# Power_Supply.net
KiCad netlist of a schematic drawn in Altium Designer
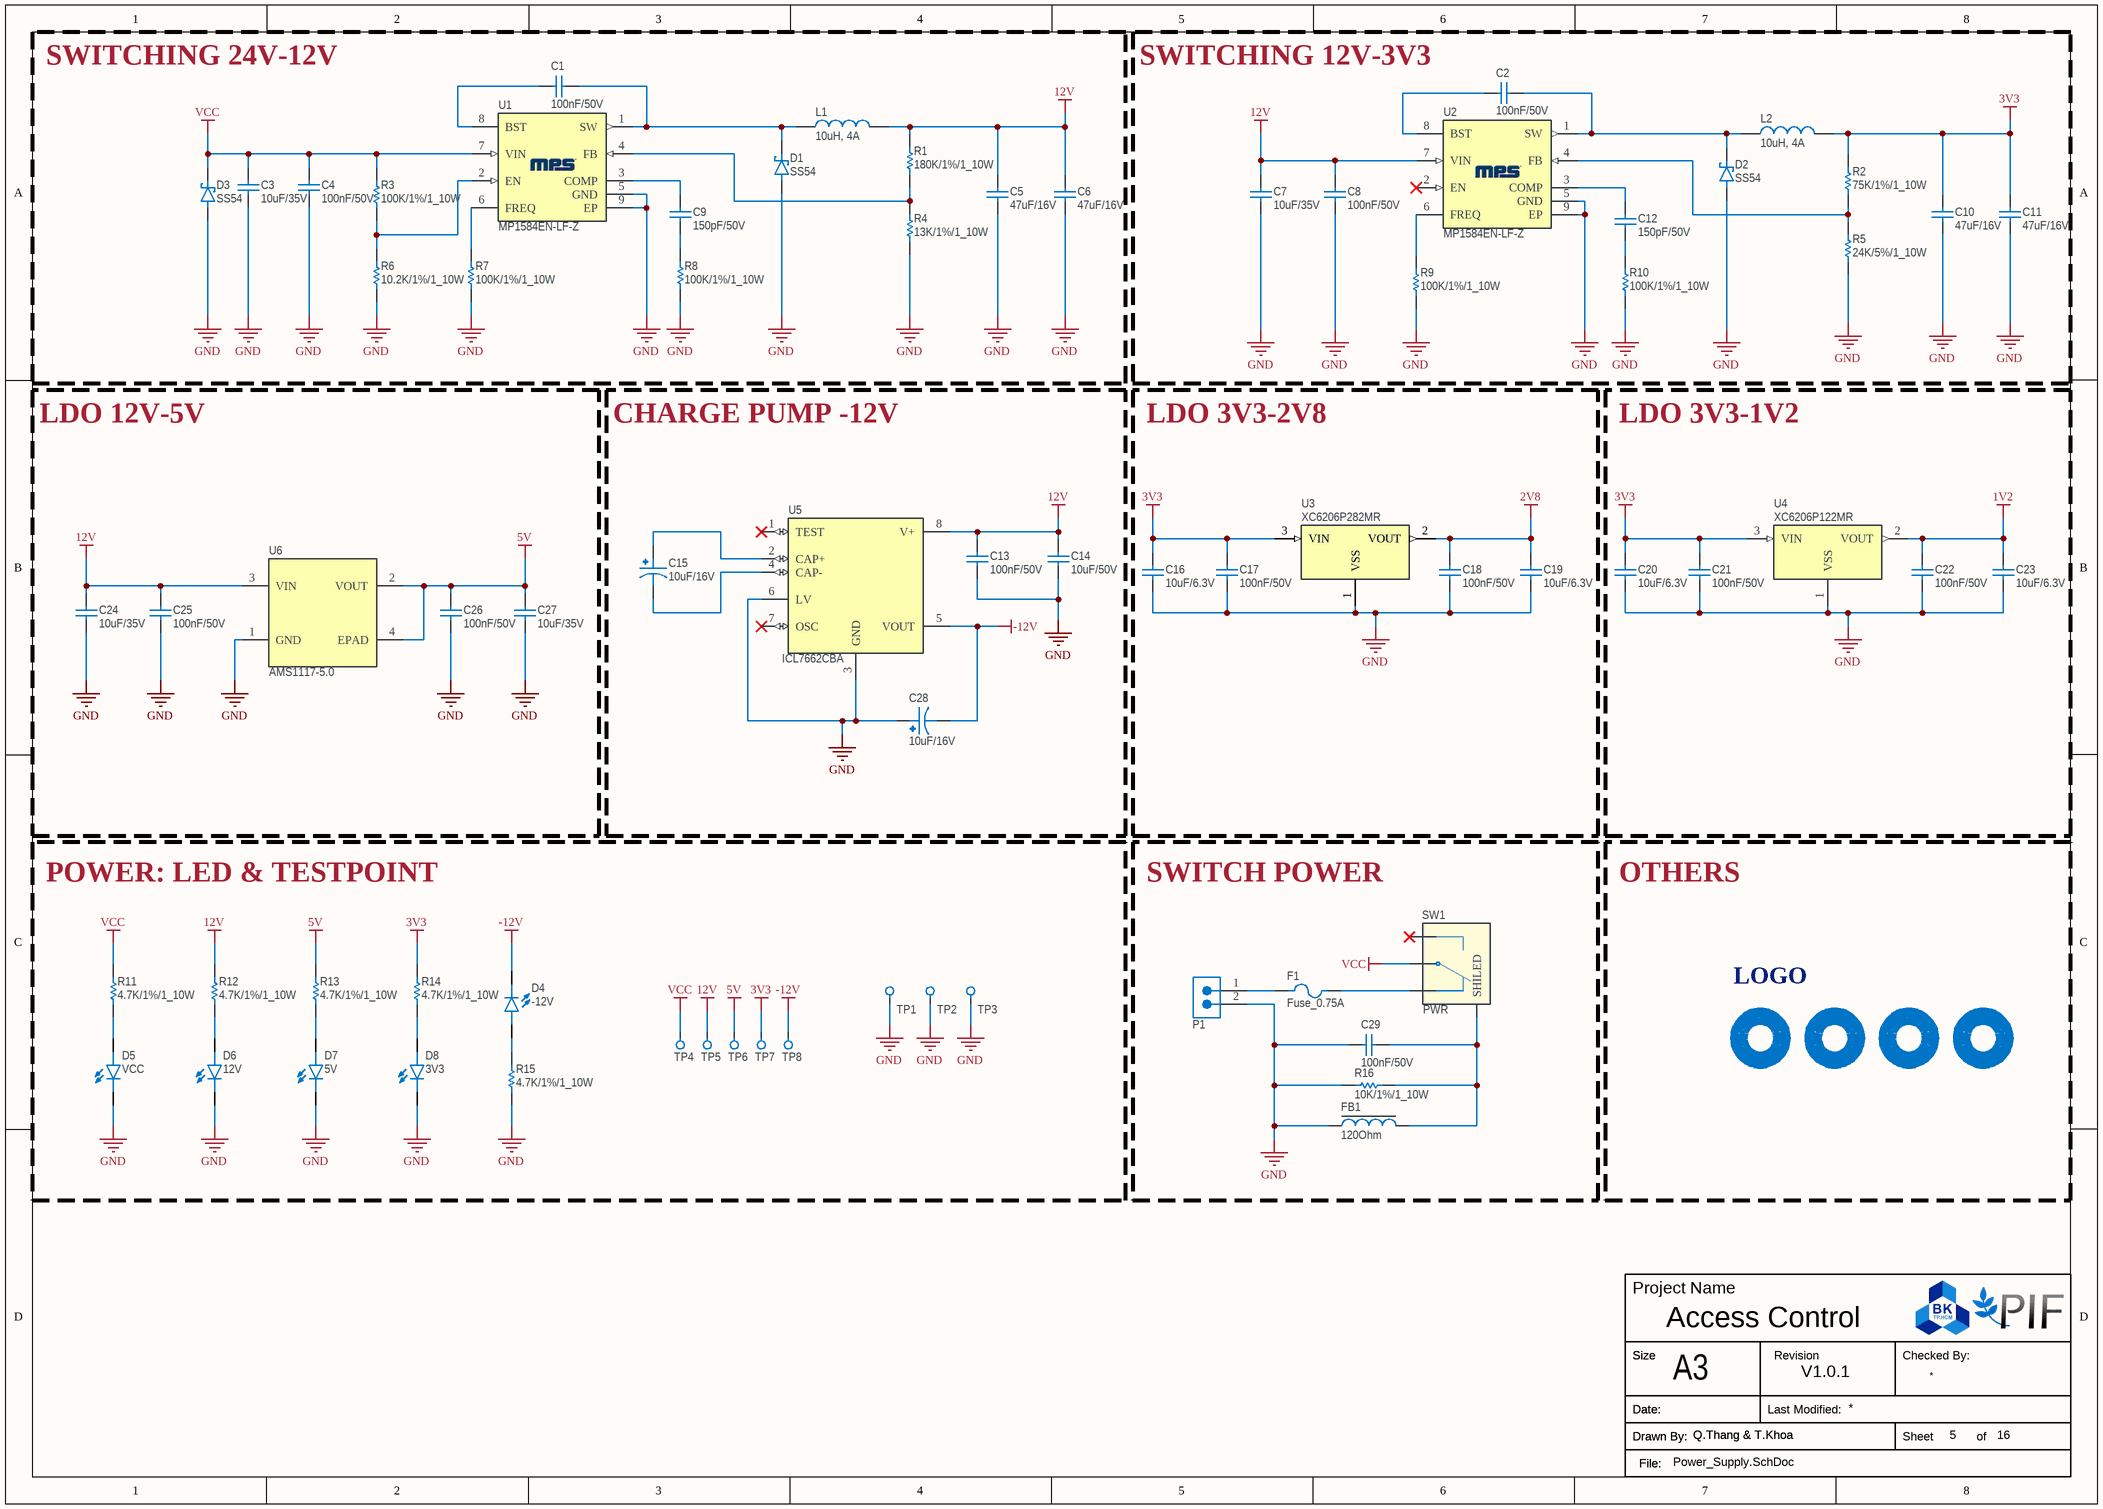
[diagram p0: Power_Supply.SchDoc]

(export (version "E")
  (design (tool "Eeschema 10.0.6"))
  (components
    (comp (ref "*1") (value "LOGO") (footprint "BK_LOGO") (libsource (lib "BluetoothTracking") (part "LOGO")))
    (comp (ref "C1")
      (value "100nF/50V")
      (footprint "CAP_0603")
      (description "CAP, size 0603, 100nF, 50V")
      (fields (field (name "SUPPLY PART NUMBER") "Tụ Gốm 0603 100nF (0.1uF) 50V"))
      (libsource (lib "BluetoothTracking") (part "Ceramic_Cap_100nF_50V_0603"))
    )
    (comp (ref "C2")
      (value "100nF/50V")
      (footprint "CAP_0603")
      (description "CAP, size 0603, 100nF, 50V")
      (fields (field (name "SUPPLY PART NUMBER") "Tụ Gốm 0603 100nF (0.1uF) 50V"))
      (libsource (lib "BluetoothTracking") (part "Ceramic_Cap_100nF_50V_0603"))
    )
    (comp (ref "C3")
      (value "10uF/35V")
      (footprint "CAP_1206")
      (description "CAP, size 1206, 10uF, 35V")
      (fields (field (name "SUPPLY PART NUMBER") "Tụ Gốm 1206 10uF 35V"))
      (libsource (lib "BluetoothTracking") (part "Ceramic_Cap_10uF_35V_1206"))
    )
    (comp (ref "C4")
      (value "100nF/50V")
      (footprint "CAP_1206")
      (description "CAP, size 1206, 100nF, 50V")
      (fields (field (name "SUPPLY PART NUMBER") "Tụ Gốm 1206 100nF (0.1uF) 50V"))
      (libsource (lib "BluetoothTracking") (part "Ceramic_Cap_100nF_50V_1206"))
    )
    (comp (ref "C5")
      (value "47uF/16V")
      (footprint "CAP_1206")
      (description "CAP, size 1206, 47uF, 16V")
      (fields (field (name "SUPPLY PART NUMBER") "Tụ Gốm 1206 47uF 16V"))
      (libsource (lib "BluetoothTracking") (part "Ceramic_Cap_47uF_16V_1206"))
    )
    (comp (ref "C6")
      (value "47uF/16V")
      (footprint "CAP_1206")
      (description "CAP, size 1206, 47uF, 16V")
      (fields (field (name "SUPPLY PART NUMBER") "Tụ Gốm 1206 47uF 16V"))
      (libsource (lib "BluetoothTracking") (part "Ceramic_Cap_47uF_16V_1206"))
    )
    (comp (ref "C7")
      (value "10uF/35V")
      (footprint "CAP_1206")
      (description "CAP, size 1206, 10uF, 35V")
      (fields (field (name "SUPPLY PART NUMBER") "Tụ Gốm 1206 10uF 35V"))
      (libsource (lib "BluetoothTracking") (part "Ceramic_Cap_10uF_35V_1206"))
    )
    (comp (ref "C8")
      (value "100nF/50V")
      (footprint "CAP_1206")
      (description "CAP, size 1206, 100nF, 50V")
      (fields (field (name "SUPPLY PART NUMBER") "Tụ Gốm 1206 100nF (0.1uF) 50V"))
      (libsource (lib "BluetoothTracking") (part "Ceramic_Cap_100nF_50V_1206"))
    )
    (comp (ref "C9")
      (value "150pF/50V")
      (footprint "CAP_0603")
      (description "CAP, size 0603, 150pF, 50V")
      (fields (field (name "SUPPLY PART NUMBER") "Tụ Gốm 0603 150pF 50V"))
      (libsource (lib "BluetoothTracking") (part "Ceramic_Cap_150pF_50V_0603"))
    )
    (comp (ref "C10")
      (value "47uF/16V")
      (footprint "CAP_1206")
      (description "CAP, size 1206, 47uF, 16V")
      (fields (field (name "SUPPLY PART NUMBER") "Tụ Gốm 1206 47uF 16V"))
      (libsource (lib "BluetoothTracking") (part "Ceramic_Cap_47uF_16V_1206"))
    )
    (comp (ref "C11")
      (value "47uF/16V")
      (footprint "CAP_1206")
      (description "CAP, size 1206, 47uF, 16V")
      (fields (field (name "SUPPLY PART NUMBER") "Tụ Gốm 1206 47uF 16V"))
      (libsource (lib "BluetoothTracking") (part "Ceramic_Cap_47uF_16V_1206"))
    )
    (comp (ref "C12")
      (value "150pF/50V")
      (footprint "CAP_0603")
      (description "CAP, size 0603, 150pF, 50V")
      (fields (field (name "SUPPLY PART NUMBER") "Tụ Gốm 0603 150pF 50V"))
      (libsource (lib "BluetoothTracking") (part "Ceramic_Cap_150pF_50V_0603"))
    )
    (comp (ref "C13")
      (value "100nF/50V")
      (footprint "CAP_0805")
      (description "CAP, size 0805, 100nF, 50V")
      (fields (field (name "SUPPLY PART NUMBER") "Tụ Gốm 0805 100nF (0.1uF) 50V"))
      (libsource (lib "BluetoothTracking") (part "Ceramic_Cap_100nF_50V_0805"))
    )
    (comp (ref "C14")
      (value "10uF/50V")
      (footprint "CAP_0805")
      (description "CAP, size 0805, 10uF, 50V")
      (fields (field (name "SUPPLY PART NUMBER") "Tụ Gốm 0805 10uF 50V"))
      (libsource (lib "BluetoothTracking") (part "Ceramic_Cap_10uF_50V_0805"))
    )
    (comp (ref "C15")
      (value "10uF/16V")
      (footprint "TanTa_Cap_A")
      (description "Tantalum Capacitors 10uF 16V 1206")
      (fields (field (name "SUPPLY PART NUMBER") "AVX"))
      (libsource (lib "") (part "Tanta_Cap_10uF_16V_1206_1"))
    )
    (comp (ref "C16")
      (value "10uF/6.3V")
      (footprint "CAP_0603")
      (description "CAP, size 0603, 10uF, 6.3V")
      (fields (field (name "SUPPLY PART NUMBER") "CC0603KRX5R5BB106"))
      (libsource (lib "BluetoothTracking") (part "Ceramic_Cap_10uF_6.3V_0603"))
    )
    (comp (ref "C17")
      (value "100nF/50V")
      (footprint "CAP_0402")
      (description "CAP, size 0402, 100nF, 50V")
      (fields (field (name "SUPPLY PART NUMBER") "Tụ Gốm 0402 100nF (0.1uF) 50V"))
      (libsource (lib "BluetoothTracking") (part "Ceramic_Cap_100nF_50V_0402"))
    )
    (comp (ref "C18")
      (value "100nF/50V")
      (footprint "CAP_0402")
      (description "CAP, size 0402, 100nF, 50V")
      (fields (field (name "SUPPLY PART NUMBER") "Tụ Gốm 0402 100nF (0.1uF) 50V"))
      (libsource (lib "BluetoothTracking") (part "Ceramic_Cap_100nF_50V_0402"))
    )
    (comp (ref "C19")
      (value "10uF/6.3V")
      (footprint "CAP_0603")
      (description "CAP, size 0603, 10uF, 6.3V")
      (fields (field (name "SUPPLY PART NUMBER") "CC0603KRX5R5BB106"))
      (libsource (lib "BluetoothTracking") (part "Ceramic_Cap_10uF_6.3V_0603"))
    )
    (comp (ref "C20")
      (value "10uF/6.3V")
      (footprint "CAP_0603")
      (description "CAP, size 0603, 10uF, 6.3V")
      (fields (field (name "SUPPLY PART NUMBER") "CC0603KRX5R5BB106"))
      (libsource (lib "BluetoothTracking") (part "Ceramic_Cap_10uF_6.3V_0603"))
    )
    (comp (ref "C21")
      (value "100nF/50V")
      (footprint "CAP_0402")
      (description "CAP, size 0402, 100nF, 50V")
      (fields (field (name "SUPPLY PART NUMBER") "Tụ Gốm 0402 100nF (0.1uF) 50V"))
      (libsource (lib "BluetoothTracking") (part "Ceramic_Cap_100nF_50V_0402"))
    )
    (comp (ref "C22")
      (value "100nF/50V")
      (footprint "CAP_0402")
      (description "CAP, size 0402, 100nF, 50V")
      (fields (field (name "SUPPLY PART NUMBER") "Tụ Gốm 0402 100nF (0.1uF) 50V"))
      (libsource (lib "BluetoothTracking") (part "Ceramic_Cap_100nF_50V_0402"))
    )
    (comp (ref "C23")
      (value "10uF/6.3V")
      (footprint "CAP_0603")
      (description "CAP, size 0603, 10uF, 6.3V")
      (fields (field (name "SUPPLY PART NUMBER") "CC0603KRX5R5BB106"))
      (libsource (lib "BluetoothTracking") (part "Ceramic_Cap_10uF_6.3V_0603"))
    )
    (comp (ref "C24")
      (value "10uF/35V")
      (footprint "CAP_1206")
      (description "CAP, size 1206, 10uF, 35V")
      (fields (field (name "SUPPLY PART NUMBER") "Tụ Gốm 1206 10uF 35V"))
      (libsource (lib "BluetoothTracking") (part "Ceramic_Cap_10uF_35V_1206"))
    )
    (comp (ref "C25")
      (value "100nF/50V")
      (footprint "CAP_1206")
      (description "CAP, size 1206, 100nF, 50V")
      (fields (field (name "SUPPLY PART NUMBER") "Tụ Gốm 1206 100nF (0.1uF) 50V"))
      (libsource (lib "BluetoothTracking") (part "Ceramic_Cap_100nF_50V_1206"))
    )
    (comp (ref "C26")
      (value "100nF/50V")
      (footprint "CAP_1206")
      (description "CAP, size 1206, 100nF, 50V")
      (fields (field (name "SUPPLY PART NUMBER") "Tụ Gốm 1206 100nF (0.1uF) 50V"))
      (libsource (lib "BluetoothTracking") (part "Ceramic_Cap_100nF_50V_1206"))
    )
    (comp (ref "C27")
      (value "10uF/35V")
      (footprint "CAP_1206")
      (description "CAP, size 1206, 10uF, 35V")
      (fields (field (name "SUPPLY PART NUMBER") "Tụ Gốm 1206 10uF 35V"))
      (libsource (lib "BluetoothTracking") (part "Ceramic_Cap_10uF_35V_1206"))
    )
    (comp (ref "C28")
      (value "10uF/16V")
      (footprint "TanTa_Cap_A")
      (description "Tantalum Capacitors 10uF 16V 1206")
      (fields (field (name "SUPPLY PART NUMBER") "AVX"))
      (libsource (lib "BluetoothTracking") (part "Tanta_Cap_10uF_16V_1206"))
    )
    (comp (ref "C29")
      (value "100nF/50V")
      (footprint "CAP_0603")
      (description "CAP, size 0603, 100nF, 50V")
      (fields (field (name "SUPPLY PART NUMBER") "Tụ Gốm 0603 100nF (0.1uF) 50V"))
      (libsource (lib "BluetoothTracking") (part "Ceramic_Cap_100nF_50V_0603"))
    )
    (comp (ref "D1")
      (value "SS54")
      (footprint "D_SMA")
      (description "Diode Schottky 40V 5A Surface Mount SMA")
      (fields (field (name "SUPPLY PART NUMBER") "SS54 SMA Diode Shotky 5A 40V"))
      (libsource (lib "BluetoothTracking") (part "Diode_SS54"))
    )
    (comp (ref "D2")
      (value "SS54")
      (footprint "D_SMA")
      (description "Diode Schottky 40V 5A Surface Mount SMA")
      (fields (field (name "SUPPLY PART NUMBER") "SS54 SMA Diode Shotky 5A 40V"))
      (libsource (lib "BluetoothTracking") (part "Diode_SS54"))
    )
    (comp (ref "D3")
      (value "SS54")
      (footprint "D_SMA")
      (description "Diode Schottky 40V 5A Surface Mount SMA")
      (fields (field (name "SUPPLY PART NUMBER") "SS54 SMA Diode Shotky 5A 40V"))
      (libsource (lib "BluetoothTracking") (part "Diode_SS54"))
    )
    (comp (ref "D4")
      (value "-12V")
      (footprint "LED_0603Y")
      (description "LED Yellow 0603")
      (fields (field (name "SUPPLY PART NUMBER") "LED Vàng 0603 Dán SMD Trong Suốt Harvatek"))
      (libsource (lib "BluetoothTracking") (part "LED_Yellow_0603"))
    )
    (comp (ref "D5")
      (value "VCC")
      (footprint "LED_0603Y")
      (description "LED Yellow 0603")
      (fields (field (name "SUPPLY PART NUMBER") "LED Vàng 0603 Dán SMD Trong Suốt Harvatek"))
      (libsource (lib "BluetoothTracking") (part "LED_Yellow_0603"))
    )
    (comp (ref "D6")
      (value "12V")
      (footprint "LED_0603Y")
      (description "LED Yellow 0603")
      (fields (field (name "SUPPLY PART NUMBER") "LED Vàng 0603 Dán SMD Trong Suốt Harvatek"))
      (libsource (lib "BluetoothTracking") (part "LED_Yellow_0603"))
    )
    (comp (ref "D7")
      (value "5V")
      (footprint "LED_0603Y")
      (description "LED Yellow 0603")
      (fields (field (name "SUPPLY PART NUMBER") "LED Vàng 0603 Dán SMD Trong Suốt Harvatek"))
      (libsource (lib "BluetoothTracking") (part "LED_Yellow_0603"))
    )
    (comp (ref "D8")
      (value "3V3")
      (footprint "LED_0603Y")
      (description "LED Yellow 0603")
      (fields (field (name "SUPPLY PART NUMBER") "LED Vàng 0603 Dán SMD Trong Suốt Harvatek"))
      (libsource (lib "BluetoothTracking") (part "LED_Yellow_0603"))
    )
    (comp (ref "F1")
      (value "Fuse_0.75A")
      (footprint "FUSER_MF-MSMF075/24-2")
      (description "MF-MSMF075/24-2 Cầu Chì Tự Phục Hồi 1812 24V 0.75A")
      (libsource (lib "BluetoothTracking") (part "Fuse_24V_0.75A_1812"))
    )
    (comp (ref "FB1")
      (value "120Ohm")
      (footprint "Ferrite_Bead_0805")
      (description "Ferrite Bead, size 0805, 120Ohm, 2A")
      (fields (field (name "SUPPLY PART NUMBER") "CBW201209U121T Ferrite Beads 2A 120 Ohm 0805"))
      (libsource (lib "BluetoothTracking") (part "Ferrite_Bead_120Ohm_2A_0805"))
    )
    (comp (ref "H1")
      (value "Mounting Hole without connection")
      (footprint "MountingHole_3.2mm_M3_Pad_Via")
      (libsource (lib "BluetoothTracking") (part "MountingHole"))
    )
    (comp (ref "H2")
      (value "Mounting Hole without connection")
      (footprint "MountingHole_3.2mm_M3_Pad_Via")
      (libsource (lib "BluetoothTracking") (part "MountingHole"))
    )
    (comp (ref "H3")
      (value "Mounting Hole without connection")
      (footprint "MountingHole_3.2mm_M3_Pad_Via")
      (libsource (lib "BluetoothTracking") (part "MountingHole"))
    )
    (comp (ref "H4")
      (value "Mounting Hole without connection")
      (footprint "MountingHole_3.2mm_M3_Pad_Via")
      (libsource (lib "BluetoothTracking") (part "MountingHole"))
    )
    (comp (ref "L1")
      (value "10uH, 4A")
      (footprint "Inductor_0630")
      (description "10uH, 4A, Size 0630")
      (fields (field (name "SUPPLY PART NUMBER") "Cuộn cảm 10UH 0630"))
      (libsource (lib "BluetoothTracking") (part "IND_10uH_0630"))
    )
    (comp (ref "L2")
      (value "10uH, 4A")
      (footprint "Inductor_0630")
      (description "10uH, 4A, Size 0630")
      (fields (field (name "SUPPLY PART NUMBER") "Cuộn cảm 10UH 0630"))
      (libsource (lib "BluetoothTracking") (part "IND_10uH_0630"))
    )
    (comp (ref "P1")
      (value "5.08mm_2P")
      (footprint "Terminal_Block_5.08mm_2P")
      (description "Terminal Block THT, pitch 5.08mm, 2p, 300V, 10A")
      (fields
        (field (name "SUPPLY PART NUMBER") "UL-5.08-2-R Terminal Block Plug-in Hàn PCB 2 Chân Cong 5.08mm 300V 15A ULO")
      )
      (libsource (lib "BluetoothTracking") (part "Terminal_Block_5.08mm_2P"))
    )
    (comp (ref "R1")
      (value "180K/1%/1_10W")
      (footprint "Resistor_0603")
      (description "Resistor 0603 180KOhm 1% 1_10W")
      (fields (field (name "SUPPLY PART NUMBER") "Điện Trở 180 KOhm 0603 1%"))
      (libsource (lib "BluetoothTracking") (part "Res_180K_0603_1%"))
    )
    (comp (ref "R2")
      (value "75K/1%/1_10W")
      (footprint "Resistor_0603")
      (description "Resistor 0603 75KOhm 1% 1_10W")
      (fields (field (name "SUPPLY PART NUMBER") "Điện Trở 75 KOhm 0603 1%"))
      (libsource (lib "BluetoothTracking") (part "Res_75K_0603_1%"))
    )
    (comp (ref "R3")
      (value "100K/1%/1_10W")
      (footprint "Resistor_0603")
      (description "Resistor 0603 100KOhm 1% 1_10W")
      (fields (field (name "SUPPLY PART NUMBER") "Điện Trở 100 KOhm 0603 1%"))
      (libsource (lib "BluetoothTracking") (part "Res_100K_0603_1%"))
    )
    (comp (ref "R4")
      (value "13K/1%/1_10W")
      (footprint "Resistor_0603")
      (description "Resistor 0603 13KOhm 1% 1_10W")
      (fields (field (name "SUPPLY PART NUMBER") "Điện Trở 13 KOhm 0603 1%"))
      (libsource (lib "BluetoothTracking") (part "Res_13K_0603_1%"))
    )
    (comp (ref "R5")
      (value "24K/5%/1_10W")
      (footprint "Resistor_0603")
      (description "Resistor 0603 24KOhm 5% 1_10W")
      (fields (field (name "SUPPLY PART NUMBER") "Điện Trở 24 KOhm 0603 5%"))
      (libsource (lib "BluetoothTracking") (part "Res_24K_0603_5%"))
    )
    (comp (ref "R6")
      (value "10.2K/1%/1_10W")
      (footprint "Resistor_0603")
      (description "Resistor 0603 10.2KOhm 1% 1_10W")
      (fields (field (name "SUPPLY PART NUMBER") "Điện Trở 10.2 KOhm 0603 1%"))
      (libsource (lib "BluetoothTracking") (part "Res_10.2K_0603_1%"))
    )
    (comp (ref "R7")
      (value "100K/1%/1_10W")
      (footprint "Resistor_0603")
      (description "Resistor 0603 100KOhm 1% 1_10W")
      (fields (field (name "SUPPLY PART NUMBER") "Điện Trở 100 KOhm 0603 1%"))
      (libsource (lib "BluetoothTracking") (part "Res_100K_0603_1%"))
    )
    (comp (ref "R8")
      (value "100K/1%/1_10W")
      (footprint "Resistor_0603")
      (description "Resistor 0603 100KOhm 1% 1_10W")
      (fields (field (name "SUPPLY PART NUMBER") "Điện Trở 100 KOhm 0603 1%"))
      (libsource (lib "BluetoothTracking") (part "Res_100K_0603_1%"))
    )
    (comp (ref "R9")
      (value "100K/1%/1_10W")
      (footprint "Resistor_0603")
      (description "Resistor 0603 100KOhm 1% 1_10W")
      (fields (field (name "SUPPLY PART NUMBER") "Điện Trở 100 KOhm 0603 1%"))
      (libsource (lib "BluetoothTracking") (part "Res_100K_0603_1%"))
    )
    (comp (ref "R10")
      (value "100K/1%/1_10W")
      (footprint "Resistor_0603")
      (description "Resistor 0603 100KOhm 1% 1_10W")
      (fields (field (name "SUPPLY PART NUMBER") "Điện Trở 100 KOhm 0603 1%"))
      (libsource (lib "BluetoothTracking") (part "Res_100K_0603_1%"))
    )
    (comp (ref "R11")
      (value "4.7K/1%/1_10W")
      (footprint "Resistor_0603")
      (description "Resistor 0603 4.7KOhm 1% 1_10W")
      (fields (field (name "SUPPLY PART NUMBER") "Điện Trở 4.7 KOhm 0603 1%"))
      (libsource (lib "BluetoothTracking") (part "Res_4.7K_0603_1%"))
    )
    (comp (ref "R12")
      (value "4.7K/1%/1_10W")
      (footprint "Resistor_0603")
      (description "Resistor 0603 4.7KOhm 1% 1_10W")
      (fields (field (name "SUPPLY PART NUMBER") "Điện Trở 4.7 KOhm 0603 1%"))
      (libsource (lib "BluetoothTracking") (part "Res_4.7K_0603_1%"))
    )
    (comp (ref "R13")
      (value "4.7K/1%/1_10W")
      (footprint "Resistor_0603")
      (description "Resistor 0603 4.7KOhm 1% 1_10W")
      (fields (field (name "SUPPLY PART NUMBER") "Điện Trở 4.7 KOhm 0603 1%"))
      (libsource (lib "BluetoothTracking") (part "Res_4.7K_0603_1%"))
    )
    (comp (ref "R14")
      (value "4.7K/1%/1_10W")
      (footprint "Resistor_0603")
      (description "Resistor 0603 4.7KOhm 1% 1_10W")
      (fields (field (name "SUPPLY PART NUMBER") "Điện Trở 4.7 KOhm 0603 1%"))
      (libsource (lib "BluetoothTracking") (part "Res_4.7K_0603_1%"))
    )
    (comp (ref "R15")
      (value "4.7K/1%/1_10W")
      (footprint "Resistor_0603")
      (description "Resistor 0603 4.7KOhm 1% 1_10W")
      (fields (field (name "SUPPLY PART NUMBER") "Điện Trở 4.7 KOhm 0603 1%"))
      (libsource (lib "BluetoothTracking") (part "Res_4.7K_0603_1%"))
    )
    (comp (ref "R16")
      (value "10K/1%/1_10W")
      (footprint "Resistor_0603")
      (description "Resistor 0603 10KOhm 1% 1_10W")
      (fields (field (name "SUPPLY PART NUMBER") "Điện Trở 10 KOhm 0603 1%"))
      (libsource (lib "BluetoothTracking") (part "Res_10K_0603_1%"))
    )
    (comp (ref "SW1")
      (value "PWR")
      (footprint "MTS-102-C3")
      (description "Switch Toggle")
      (fields
        (field (name "SUPPLY PART NUMBER") "MTS-102-C3 Công Tắc Toggle ON-ON Gạt Giữ 3 Chân Cong 6A 125VAC")
      )
      (libsource (lib "BluetoothTracking") (part "MTS-102-C3"))
    )
    (comp (ref "TP1")
      (value "GND1")
      (footprint "TestPoint_Pad_3.0x3.0mm")
      (libsource (lib "BluetoothTracking") (part "Testpoint_SMD"))
    )
    (comp (ref "TP2")
      (value "GND2")
      (footprint "TestPoint_Pad_3.0x3.0mm")
      (libsource (lib "BluetoothTracking") (part "Testpoint_SMD"))
    )
    (comp (ref "TP3")
      (value "GND3")
      (footprint "TestPoint_Pad_3.0x3.0mm")
      (libsource (lib "BluetoothTracking") (part "Testpoint_SMD"))
    )
    (comp (ref "TP4")
      (value "VCC")
      (footprint "TestPoint_Pad_3.0x3.0mm")
      (libsource (lib "BluetoothTracking") (part "Testpoint_SMD"))
    )
    (comp (ref "TP5")
      (value "12V")
      (footprint "TestPoint_Pad_3.0x3.0mm")
      (libsource (lib "BluetoothTracking") (part "Testpoint_SMD"))
    )
    (comp (ref "TP6")
      (value "5V")
      (footprint "TestPoint_Pad_3.0x3.0mm")
      (libsource (lib "BluetoothTracking") (part "Testpoint_SMD"))
    )
    (comp (ref "TP7")
      (value "3V3")
      (footprint "TestPoint_Pad_3.0x3.0mm")
      (libsource (lib "BluetoothTracking") (part "Testpoint_SMD"))
    )
    (comp (ref "TP8")
      (value "3V3")
      (footprint "TestPoint_Pad_3.0x3.0mm")
      (libsource (lib "BluetoothTracking") (part "Testpoint_SMD"))
    )
    (comp (ref "U1")
      (value "MP1584EN-LF-Z")
      (footprint "SOIC-8E")
      (libsource (lib "BluetoothTracking") (part "MP1584EN-LF-Z"))
    )
    (comp (ref "U2")
      (value "MP1584EN-LF-Z")
      (footprint "SOIC-8E")
      (libsource (lib "BluetoothTracking") (part "MP1584EN-LF-Z"))
    )
    (comp (ref "U3")
      (value "XC6206P282MR")
      (footprint "SOT-23")
      (description "LDO Regulator IC 2.8V")
      (fields (field (name "SUPPLY PART NUMBER") "IC nguồn XC6206P282MR XC6206-2.8V SOT-23"))
      (libsource (lib "BluetoothTracking") (part "XC6206P282MR"))
    )
    (comp (ref "U4")
      (value "XC6206P122MR")
      (footprint "SOT-23")
      (description "LDO Regulator IC 1.2V")
      (fields (field (name "SUPPLY PART NUMBER") "IC nguồn XC6206P122MR XC6206-1.2V SOT-23"))
      (libsource (lib "BluetoothTracking") (part "XC6206P122MR"))
    )
    (comp (ref "U5")
      (value "ICL7662CBA")
      (footprint "SOIC-8")
      (description "Vin: 4.5V ~ 20V, Vout: -Vin, 8-SOIC")
      (fields (field (name "SUPPLY PART NUMBER") "IC Dán ICL7662"))
      (libsource (lib "BluetoothTracking") (part "ICL7662CBA"))
    )
    (comp (ref "U6")
      (value "AMS1117-5.0")
      (footprint "SOT-223")
      (description "5.0V 1A Low dropout (LDO) Voltage Regulator")
      (libsource (lib "BluetoothTracking") (part "AMS1117-5.0"))
    )
  )
  (nets
    (net (code "1") (name "-12V") (class "Default")
      (node (ref "C28") (pin "2") (pinfunction "2_2") (pintype "passive"))
      (node (ref "D4") (pin "C") (pinfunction "C_C") (pintype "passive"))
      (node (ref "TP8") (pin "1") (pinfunction "1_1") (pintype "passive"))
      (node (ref "U5") (pin "5") (pinfunction "VOUT_5") (pintype "power_in"))
    )
    (net (code "2") (name "1V2") (class "Default")
      (node (ref "C22") (pin "2") (pinfunction "2_2") (pintype "passive"))
      (node (ref "C23") (pin "2") (pinfunction "2_2") (pintype "passive"))
      (node (ref "U4") (pin "2") (pinfunction "VOUT_2") (pintype "output"))
    )
    (net (code "3") (name "2V8") (class "Default")
      (node (ref "C18") (pin "2") (pinfunction "2_2") (pintype "passive"))
      (node (ref "C19") (pin "2") (pinfunction "2_2") (pintype "passive"))
      (node (ref "U3") (pin "2") (pinfunction "VOUT_2") (pintype "output"))
    )
    (net (code "4") (name "3V3") (class "Default")
      (node (ref "C10") (pin "2") (pinfunction "2_2") (pintype "passive"))
      (node (ref "C11") (pin "2") (pinfunction "2_2") (pintype "passive"))
      (node (ref "C16") (pin "2") (pinfunction "2_2") (pintype "passive"))
      (node (ref "C17") (pin "2") (pinfunction "2_2") (pintype "passive"))
      (node (ref "C20") (pin "2") (pinfunction "2_2") (pintype "passive"))
      (node (ref "C21") (pin "2") (pinfunction "2_2") (pintype "passive"))
      (node (ref "L2") (pin "2") (pinfunction "2_2") (pintype "passive"))
      (node (ref "R14") (pin "2") (pinfunction "2_2") (pintype "passive"))
      (node (ref "R2") (pin "2") (pinfunction "2_2") (pintype "passive"))
      (node (ref "TP7") (pin "1") (pinfunction "1_1") (pintype "passive"))
      (node (ref "U3") (pin "3") (pinfunction "VIN_3") (pintype "input"))
      (node (ref "U4") (pin "3") (pinfunction "VIN_3") (pintype "input"))
    )
    (net (code "5") (name "5V") (class "Default")
      (node (ref "C26") (pin "2") (pinfunction "2_2") (pintype "passive"))
      (node (ref "C27") (pin "2") (pinfunction "2_2") (pintype "passive"))
      (node (ref "R13") (pin "2") (pinfunction "2_2") (pintype "passive"))
      (node (ref "TP6") (pin "1") (pinfunction "1_1") (pintype "passive"))
      (node (ref "U6") (pin "2") (pinfunction "VOUT_2") (pintype "power_in"))
      (node (ref "U6") (pin "4") (pinfunction "EPAD_4") (pintype "power_in"))
    )
    (net (code "6") (name "12V") (class "Default")
      (node (ref "C13") (pin "2") (pinfunction "2_2") (pintype "passive"))
      (node (ref "C14") (pin "2") (pinfunction "2_2") (pintype "passive"))
      (node (ref "C24") (pin "2") (pinfunction "2_2") (pintype "passive"))
      (node (ref "C25") (pin "2") (pinfunction "2_2") (pintype "passive"))
      (node (ref "C5") (pin "2") (pinfunction "2_2") (pintype "passive"))
      (node (ref "C6") (pin "2") (pinfunction "2_2") (pintype "passive"))
      (node (ref "C7") (pin "2") (pinfunction "2_2") (pintype "passive"))
      (node (ref "C8") (pin "2") (pinfunction "2_2") (pintype "passive"))
      (node (ref "L1") (pin "2") (pinfunction "2_2") (pintype "passive"))
      (node (ref "R1") (pin "2") (pinfunction "2_2") (pintype "passive"))
      (node (ref "R12") (pin "2") (pinfunction "2_2") (pintype "passive"))
      (node (ref "TP5") (pin "1") (pinfunction "1_1") (pintype "passive"))
      (node (ref "U2") (pin "7") (pinfunction "VIN_7") (pintype "input"))
      (node (ref "U5") (pin "8") (pinfunction "V+_8") (pintype "power_in"))
      (node (ref "U6") (pin "3") (pinfunction "VIN_3") (pintype "power_in"))
    )
    (net (code "7") (name "GND") (class "Default")
      (node (ref "C10") (pin "1") (pinfunction "1_1") (pintype "passive"))
      (node (ref "C11") (pin "1") (pinfunction "1_1") (pintype "passive"))
      (node (ref "C13") (pin "1") (pinfunction "1_1") (pintype "passive"))
      (node (ref "C14") (pin "1") (pinfunction "1_1") (pintype "passive"))
      (node (ref "C16") (pin "1") (pinfunction "1_1") (pintype "passive"))
      (node (ref "C17") (pin "1") (pinfunction "1_1") (pintype "passive"))
      (node (ref "C18") (pin "1") (pinfunction "1_1") (pintype "passive"))
      (node (ref "C19") (pin "1") (pinfunction "1_1") (pintype "passive"))
      (node (ref "C20") (pin "1") (pinfunction "1_1") (pintype "passive"))
      (node (ref "C21") (pin "1") (pinfunction "1_1") (pintype "passive"))
      (node (ref "C22") (pin "1") (pinfunction "1_1") (pintype "passive"))
      (node (ref "C23") (pin "1") (pinfunction "1_1") (pintype "passive"))
      (node (ref "C24") (pin "1") (pinfunction "1_1") (pintype "passive"))
      (node (ref "C25") (pin "1") (pinfunction "1_1") (pintype "passive"))
      (node (ref "C26") (pin "1") (pinfunction "1_1") (pintype "passive"))
      (node (ref "C27") (pin "1") (pinfunction "1_1") (pintype "passive"))
      (node (ref "C28") (pin "1") (pinfunction "1_1") (pintype "passive"))
      (node (ref "C29") (pin "1") (pinfunction "1_1") (pintype "passive"))
      (node (ref "C3") (pin "1") (pinfunction "1_1") (pintype "passive"))
      (node (ref "C4") (pin "1") (pinfunction "1_1") (pintype "passive"))
      (node (ref "C5") (pin "1") (pinfunction "1_1") (pintype "passive"))
      (node (ref "C6") (pin "1") (pinfunction "1_1") (pintype "passive"))
      (node (ref "C7") (pin "1") (pinfunction "1_1") (pintype "passive"))
      (node (ref "C8") (pin "1") (pinfunction "1_1") (pintype "passive"))
      (node (ref "D1") (pin "2") (pinfunction "A_2") (pintype "passive"))
      (node (ref "D2") (pin "2") (pinfunction "A_2") (pintype "passive"))
      (node (ref "D3") (pin "2") (pinfunction "A_2") (pintype "passive"))
      (node (ref "D5") (pin "C") (pinfunction "C_C") (pintype "passive"))
      (node (ref "D6") (pin "C") (pinfunction "C_C") (pintype "passive"))
      (node (ref "D7") (pin "C") (pinfunction "C_C") (pintype "passive"))
      (node (ref "D8") (pin "C") (pinfunction "C_C") (pintype "passive"))
      (node (ref "FB1") (pin "2") (pinfunction "2_2") (pintype "passive"))
      (node (ref "P1") (pin "2") (pinfunction "2_2") (pintype "passive"))
      (node (ref "R10") (pin "1") (pinfunction "1_1") (pintype "passive"))
      (node (ref "R15") (pin "2") (pinfunction "2_2") (pintype "passive"))
      (node (ref "R16") (pin "1") (pinfunction "1_1") (pintype "passive"))
      (node (ref "R4") (pin "1") (pinfunction "1_1") (pintype "passive"))
      (node (ref "R5") (pin "1") (pinfunction "1_1") (pintype "passive"))
      (node (ref "R6") (pin "1") (pinfunction "1_1") (pintype "passive"))
      (node (ref "R7") (pin "1") (pinfunction "1_1") (pintype "passive"))
      (node (ref "R8") (pin "1") (pinfunction "1_1") (pintype "passive"))
      (node (ref "R9") (pin "1") (pinfunction "1_1") (pintype "passive"))
      (node (ref "TP1") (pin "1") (pinfunction "1_1") (pintype "passive"))
      (node (ref "TP2") (pin "1") (pinfunction "1_1") (pintype "passive"))
      (node (ref "TP3") (pin "1") (pinfunction "1_1") (pintype "passive"))
      (node (ref "U1") (pin "5") (pinfunction "GND_5") (pintype "passive"))
      (node (ref "U1") (pin "9") (pinfunction "EP_9") (pintype "passive"))
      (node (ref "U2") (pin "5") (pinfunction "GND_5") (pintype "passive"))
      (node (ref "U2") (pin "9") (pinfunction "EP_9") (pintype "passive"))
      (node (ref "U3") (pin "1") (pinfunction "VSS_1") (pintype "passive"))
      (node (ref "U4") (pin "1") (pinfunction "VSS_1") (pintype "passive"))
      (node (ref "U5") (pin "3") (pinfunction "GND_3") (pintype "passive"))
      (node (ref "U5") (pin "6") (pinfunction "LV_6") (pintype "power_in"))
      (node (ref "U6") (pin "1") (pinfunction "GND_1") (pintype "passive"))
    )
    (net (code "8") (name "Net-(C9-Pad1)") (class "Default")
      (node (ref "C9") (pin "1") (pinfunction "1_1") (pintype "passive"))
      (node (ref "R8") (pin "2") (pinfunction "2_2") (pintype "passive"))
    )
    (net (code "9") (name "Net-(C12-Pad1)") (class "Default")
      (node (ref "C12") (pin "1") (pinfunction "1_1") (pintype "passive"))
      (node (ref "R10") (pin "2") (pinfunction "2_2") (pintype "passive"))
    )
    (net (code "10") (name "Net-(D1-C)") (class "Default")
      (node (ref "C1") (pin "2") (pinfunction "2_2") (pintype "passive"))
      (node (ref "D1") (pin "1") (pinfunction "C_1") (pintype "passive"))
      (node (ref "L1") (pin "1") (pinfunction "1_1") (pintype "passive"))
      (node (ref "U1") (pin "1") (pinfunction "SW_1") (pintype "output"))
    )
    (net (code "11") (name "Net-(D2-C)") (class "Default")
      (node (ref "C2") (pin "2") (pinfunction "2_2") (pintype "passive"))
      (node (ref "D2") (pin "1") (pinfunction "C_1") (pintype "passive"))
      (node (ref "L2") (pin "1") (pinfunction "1_1") (pintype "passive"))
      (node (ref "U2") (pin "1") (pinfunction "SW_1") (pintype "output"))
    )
    (net (code "12") (name "Net-(D4-PadA)") (class "Default")
      (node (ref "D4") (pin "A") (pinfunction "A_A") (pintype "passive"))
      (node (ref "R15") (pin "1") (pinfunction "1_1") (pintype "passive"))
    )
    (net (code "13") (name "Net-(D5-PadA)") (class "Default")
      (node (ref "D5") (pin "A") (pinfunction "A_A") (pintype "passive"))
      (node (ref "R11") (pin "1") (pinfunction "1_1") (pintype "passive"))
    )
    (net (code "14") (name "Net-(D6-PadA)") (class "Default")
      (node (ref "D6") (pin "A") (pinfunction "A_A") (pintype "passive"))
      (node (ref "R12") (pin "1") (pinfunction "1_1") (pintype "passive"))
    )
    (net (code "15") (name "Net-(D7-PadA)") (class "Default")
      (node (ref "D7") (pin "A") (pinfunction "A_A") (pintype "passive"))
      (node (ref "R13") (pin "1") (pinfunction "1_1") (pintype "passive"))
    )
    (net (code "16") (name "Net-(D8-PadA)") (class "Default")
      (node (ref "D8") (pin "A") (pinfunction "A_A") (pintype "passive"))
      (node (ref "R14") (pin "1") (pinfunction "1_1") (pintype "passive"))
    )
    (net (code "17") (name "Net-(F1-Pad1)") (class "Default")
      (node (ref "F1") (pin "1") (pinfunction "1_1") (pintype "passive"))
      (node (ref "P1") (pin "1") (pinfunction "1_1") (pintype "passive"))
    )
    (net (code "18") (name "Net-(F1-Pad2)") (class "Default")
      (node (ref "F1") (pin "2") (pinfunction "2_2") (pintype "passive"))
      (node (ref "SW1") (pin "1") (pinfunction "1_1") (pintype "passive"))
    )
    (net (code "19") (name "Net-(SW1-SHILED)") (class "Default")
      (node (ref "C29") (pin "2") (pinfunction "2_2") (pintype "passive"))
      (node (ref "FB1") (pin "1") (pinfunction "1_1") (pintype "passive"))
      (node (ref "R16") (pin "2") (pinfunction "2_2") (pintype "passive"))
      (node (ref "SW1") (pin "SH") (pinfunction "SHILED_SH") (pintype "passive"))
    )
    (net (code "20") (name "Net-(U1-BST)") (class "Default")
      (node (ref "C1") (pin "1") (pinfunction "1_1") (pintype "passive"))
      (node (ref "U1") (pin "8") (pinfunction "BST_8") (pintype "passive"))
    )
    (net (code "21") (name "Net-(U1-COMP)") (class "Default")
      (node (ref "C9") (pin "2") (pinfunction "2_2") (pintype "passive"))
      (node (ref "U1") (pin "3") (pinfunction "COMP_3") (pintype "passive"))
    )
    (net (code "22") (name "Net-(U1-EN)") (class "Default")
      (node (ref "R3") (pin "1") (pinfunction "1_1") (pintype "passive"))
      (node (ref "R6") (pin "2") (pinfunction "2_2") (pintype "passive"))
      (node (ref "U1") (pin "2") (pinfunction "EN_2") (pintype "input"))
    )
    (net (code "23") (name "Net-(U1-FB)") (class "Default")
      (node (ref "R1") (pin "1") (pinfunction "1_1") (pintype "passive"))
      (node (ref "R4") (pin "2") (pinfunction "2_2") (pintype "passive"))
      (node (ref "U1") (pin "4") (pinfunction "FB_4") (pintype "input"))
    )
    (net (code "24") (name "Net-(U1-FREQ)") (class "Default")
      (node (ref "R7") (pin "2") (pinfunction "2_2") (pintype "passive"))
      (node (ref "U1") (pin "6") (pinfunction "FREQ_6") (pintype "passive"))
    )
    (net (code "25") (name "Net-(U2-BST)") (class "Default")
      (node (ref "C2") (pin "1") (pinfunction "1_1") (pintype "passive"))
      (node (ref "U2") (pin "8") (pinfunction "BST_8") (pintype "passive"))
    )
    (net (code "26") (name "Net-(U2-COMP)") (class "Default")
      (node (ref "C12") (pin "2") (pinfunction "2_2") (pintype "passive"))
      (node (ref "U2") (pin "3") (pinfunction "COMP_3") (pintype "passive"))
    )
    (net (code "27") (name "Net-(U2-FB)") (class "Default")
      (node (ref "R2") (pin "1") (pinfunction "1_1") (pintype "passive"))
      (node (ref "R5") (pin "2") (pinfunction "2_2") (pintype "passive"))
      (node (ref "U2") (pin "4") (pinfunction "FB_4") (pintype "input"))
    )
    (net (code "28") (name "Net-(U2-FREQ)") (class "Default")
      (node (ref "R9") (pin "2") (pinfunction "2_2") (pintype "passive"))
      (node (ref "U2") (pin "6") (pinfunction "FREQ_6") (pintype "passive"))
    )
    (net (code "29") (name "Net-(U5-CAP+)") (class "Default")
      (node (ref "C15") (pin "1") (pinfunction "1_1") (pintype "passive"))
      (node (ref "U5") (pin "2") (pinfunction "CAP+_2") (pintype "bidirectional"))
    )
    (net (code "30") (name "Net-(U5-CAP-)") (class "Default")
      (node (ref "C15") (pin "2") (pinfunction "2_2") (pintype "passive"))
      (node (ref "U5") (pin "4") (pinfunction "CAP-_4") (pintype "bidirectional"))
    )
    (net (code "31") (name "VCC") (class "Default")
      (node (ref "C3") (pin "2") (pinfunction "2_2") (pintype "passive"))
      (node (ref "C4") (pin "2") (pinfunction "2_2") (pintype "passive"))
      (node (ref "D3") (pin "1") (pinfunction "C_1") (pintype "passive"))
      (node (ref "R11") (pin "2") (pinfunction "2_2") (pintype "passive"))
      (node (ref "R3") (pin "2") (pinfunction "2_2") (pintype "passive"))
      (node (ref "SW1") (pin "2") (pinfunction "2_2") (pintype "passive"))
      (node (ref "TP4") (pin "1") (pinfunction "1_1") (pintype "passive"))
      (node (ref "U1") (pin "7") (pinfunction "VIN_7") (pintype "input"))
    )
    (net (code "32") (name "unconnected-(SW1-Pad3)") (class "Default")
      (node (ref "SW1") (pin "3") (pinfunction "3_3") (pintype "passive+no_connect"))
    )
    (net (code "33") (name "unconnected-(U2-EN-Pad2)") (class "Default")
      (node (ref "U2") (pin "2") (pinfunction "EN_2") (pintype "input+no_connect"))
    )
    (net (code "34") (name "unconnected-(U5-OSC-Pad7)") (class "Default")
      (node (ref "U5") (pin "7") (pinfunction "OSC_7") (pintype "bidirectional+no_connect"))
    )
    (net (code "35") (name "unconnected-(U5-TEST-Pad1)") (class "Default")
      (node (ref "U5") (pin "1") (pinfunction "TEST_1") (pintype "bidirectional+no_connect"))
    )
  )
)
